# bonnet_floral.net
KiCad netlist of a schematic drawn in EAGLE
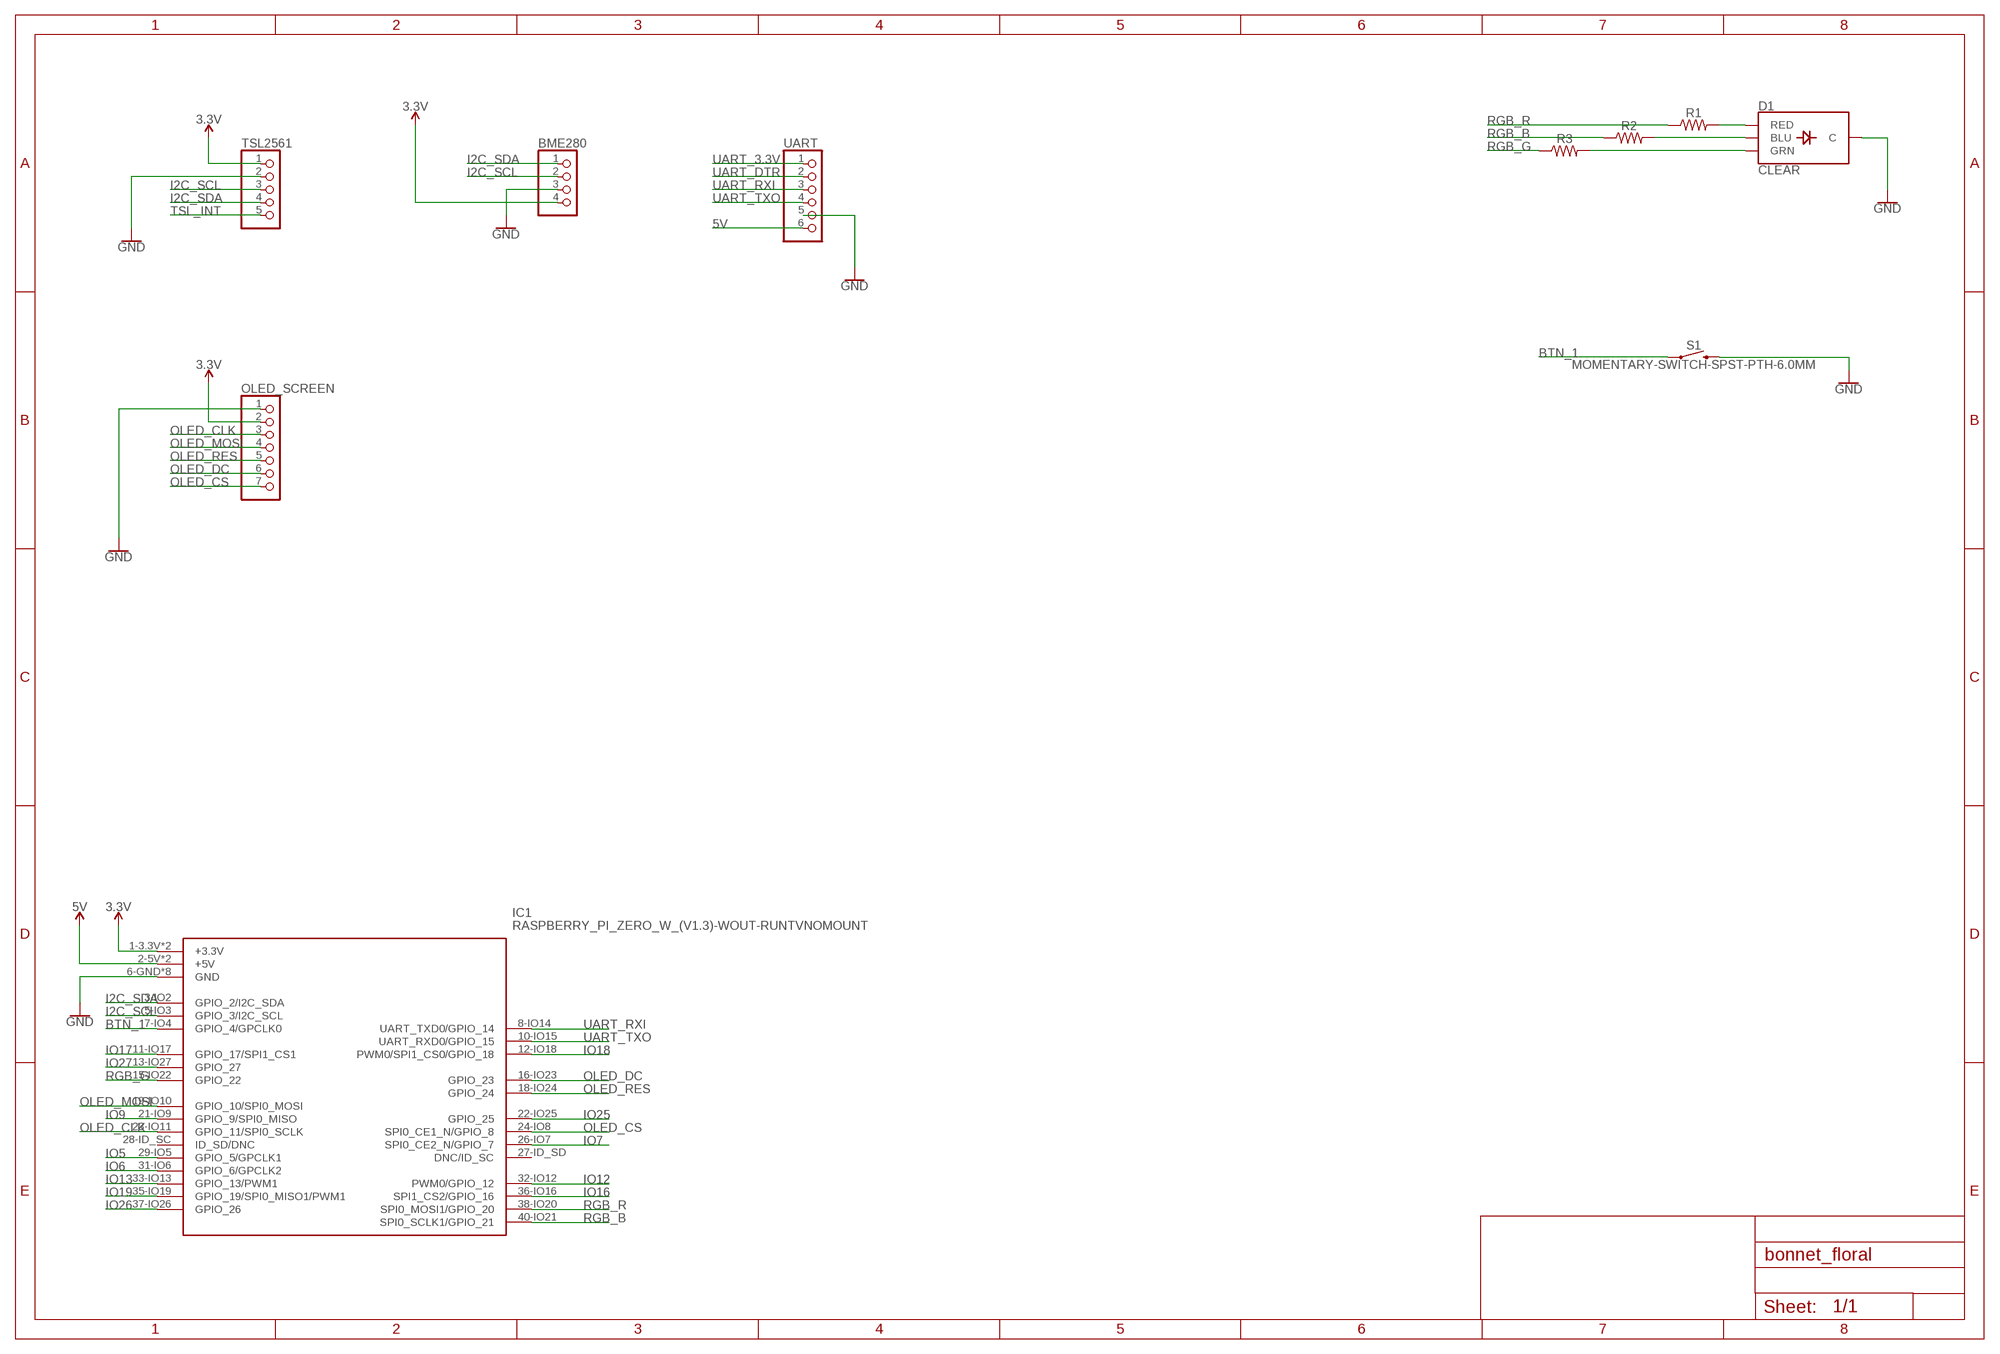
[diagram p0: schematic, sheet 1]

(export (version "E")
  (design (tool "Eeschema 10.0.6"))
  (components
    (comp (ref "BME280")
      (value "PINHD-1X4")
      (footprint "eagle-import:1X04")
      (libsource (lib "eagle-import") (part "PINHD-1X4"))
    )
    (comp (ref "D1")
      (value "CLEAR")
      (footprint "eagle-import:LED-RGB-THRU@1")
      (libsource (lib "eagle-import") (part "LED-RGB-CCCLEAR"))
    )
    (comp (ref "IC1")
      (value "RASPBERRY_PI_ZERO_W_(V1.3)-WOUT-RUNTVNOMOUNT")
      (footprint "eagle-import:RASPBERRYPIZEROWV13-WOUT-RUNTV-NOMOUNT")
      (libsource (lib "eagle-import") (part "RASPBERRY_PI_ZERO_W_(V1.3)-WOUT-RUNTVNOMOUNT"))
    )
    (comp (ref "OLED_SCREEN")
      (value "PINHD-1X7")
      (footprint "eagle-import:1X07")
      (libsource (lib "eagle-import") (part "PINHD-1X7"))
    )
    (comp (ref "R1")
      (value "RESISTORAXIAL-0.3")
      (footprint "eagle-import:AXIAL-0.3")
      (libsource (lib "eagle-import") (part "RESISTORAXIAL-0.3"))
    )
    (comp (ref "R2")
      (value "RESISTORAXIAL-0.3")
      (footprint "eagle-import:AXIAL-0.3")
      (libsource (lib "eagle-import") (part "RESISTORAXIAL-0.3"))
    )
    (comp (ref "R3")
      (value "RESISTORAXIAL-0.3")
      (footprint "eagle-import:AXIAL-0.3")
      (libsource (lib "eagle-import") (part "RESISTORAXIAL-0.3"))
    )
    (comp (ref "S1")
      (value "MOMENTARY-SWITCH-SPST-PTH-6.0MM")
      (footprint "eagle-import:TACTILE_SWITCH_PTH_6.0MM")
      (libsource (lib "eagle-import") (part "MOMENTARY-SWITCH-SPST-PTH-6.0MM"))
    )
    (comp (ref "TSL2561")
      (value "PINHD-1X5")
      (footprint "eagle-import:1X05")
      (libsource (lib "eagle-import") (part "PINHD-1X5"))
    )
    (comp (ref "UART")
      (value "PINHD-1X6")
      (footprint "eagle-import:1X06")
      (libsource (lib "eagle-import") (part "PINHD-1X6"))
    )
  )
  (nets
    (net (code "1") (name "/BTN_1") (class "Default")
      (node (ref "IC1") (pin "7-IO4") (pinfunction "GPIO_4/GPCLK0_7-IO4") (pintype "bidirectional"))
      (node (ref "S1") (pin "1") (pinfunction "1_1") (pintype "passive"))
    )
    (net (code "2") (name "/I2C_SCL") (class "Default")
      (node (ref "BME280") (pin "2") (pinfunction "2_2") (pintype "passive"))
      (node (ref "IC1") (pin "5-IO3") (pinfunction "GPIO_3/I2C_SCL_5-IO3") (pintype "bidirectional"))
      (node (ref "TSL2561") (pin "3") (pinfunction "3_3") (pintype "passive"))
    )
    (net (code "3") (name "/I2C_SDA") (class "Default")
      (node (ref "BME280") (pin "1") (pinfunction "1_1") (pintype "passive"))
      (node (ref "IC1") (pin "3-IO2") (pinfunction "GPIO_2/I2C_SDA_3-IO2") (pintype "bidirectional"))
      (node (ref "TSL2561") (pin "4") (pinfunction "4_4") (pintype "passive"))
    )
    (net (code "4") (name "/IO5") (class "Default")
      (node (ref "IC1") (pin "29-IO5") (pinfunction "GPIO_5/GPCLK1_29-IO5") (pintype "bidirectional"))
    )
    (net (code "5") (name "/IO6") (class "Default")
      (node (ref "IC1") (pin "31-IO6") (pinfunction "GPIO_6/GPCLK2_31-IO6") (pintype "bidirectional"))
    )
    (net (code "6") (name "/IO7") (class "Default")
      (node (ref "IC1") (pin "26-IO7") (pinfunction "SPI0_CE2_N/GPIO_7_26-IO7") (pintype "bidirectional"))
    )
    (net (code "7") (name "/IO9") (class "Default")
      (node (ref "IC1") (pin "21-IO9") (pinfunction "GPIO_9/SPI0_MISO_21-IO9") (pintype "bidirectional"))
    )
    (net (code "8") (name "/IO12") (class "Default")
      (node (ref "IC1") (pin "32-IO12") (pinfunction "PWM0/GPIO_12_32-IO12") (pintype "bidirectional"))
    )
    (net (code "9") (name "/IO13") (class "Default")
      (node (ref "IC1") (pin "33-IO13") (pinfunction "GPIO_13/PWM1_33-IO13") (pintype "bidirectional"))
    )
    (net (code "10") (name "/IO16") (class "Default")
      (node (ref "IC1") (pin "36-IO16") (pinfunction "SPI1_CS2/GPIO_16_36-IO16") (pintype "bidirectional"))
    )
    (net (code "11") (name "/IO17") (class "Default")
      (node (ref "IC1") (pin "11-IO17") (pinfunction "GPIO_17/SPI1_CS1_11-IO17") (pintype "bidirectional"))
    )
    (net (code "12") (name "/IO18") (class "Default")
      (node (ref "IC1") (pin "12-IO18") (pinfunction "PWM0/SPI1_CS0/GPIO_18_12-IO18") (pintype "bidirectional"))
    )
    (net (code "13") (name "/IO19") (class "Default")
      (node (ref "IC1") (pin "35-IO19") (pinfunction "GPIO_19/SPI0_MISO1/PWM1_35-IO19") (pintype "bidirectional"))
    )
    (net (code "14") (name "/IO25") (class "Default")
      (node (ref "IC1") (pin "22-IO25") (pinfunction "GPIO_25_22-IO25") (pintype "bidirectional"))
    )
    (net (code "15") (name "/IO26") (class "Default")
      (node (ref "IC1") (pin "37-IO26") (pinfunction "GPIO_26_37-IO26") (pintype "bidirectional"))
    )
    (net (code "16") (name "/IO27") (class "Default")
      (node (ref "IC1") (pin "13-IO27") (pinfunction "GPIO_27_13-IO27") (pintype "bidirectional"))
    )
    (net (code "17") (name "/OLED_CLK") (class "Default")
      (node (ref "IC1") (pin "23-IO11") (pinfunction "GPIO_11/SPI0_SCLK_23-IO11") (pintype "bidirectional"))
      (node (ref "OLED_SCREEN") (pin "3") (pinfunction "3_3") (pintype "passive"))
    )
    (net (code "18") (name "/OLED_CS") (class "Default")
      (node (ref "IC1") (pin "24-IO8") (pinfunction "SPI0_CE1_N/GPIO_8_24-IO8") (pintype "bidirectional"))
      (node (ref "OLED_SCREEN") (pin "7") (pinfunction "7_7") (pintype "passive"))
    )
    (net (code "19") (name "/OLED_DC") (class "Default")
      (node (ref "IC1") (pin "16-IO23") (pinfunction "GPIO_23_16-IO23") (pintype "bidirectional"))
      (node (ref "OLED_SCREEN") (pin "6") (pinfunction "6_6") (pintype "passive"))
    )
    (net (code "20") (name "/OLED_MOSI") (class "Default")
      (node (ref "IC1") (pin "19-IO10") (pinfunction "GPIO_10/SPI0_MOSI_19-IO10") (pintype "bidirectional"))
      (node (ref "OLED_SCREEN") (pin "4") (pinfunction "4_4") (pintype "passive"))
    )
    (net (code "21") (name "/OLED_RES") (class "Default")
      (node (ref "IC1") (pin "18-IO24") (pinfunction "GPIO_24_18-IO24") (pintype "bidirectional"))
      (node (ref "OLED_SCREEN") (pin "5") (pinfunction "5_5") (pintype "passive"))
    )
    (net (code "22") (name "/RGB_B") (class "Default")
      (node (ref "IC1") (pin "40-IO21") (pinfunction "SPI0_SCLK1/GPIO_21_40-IO21") (pintype "bidirectional"))
      (node (ref "R2") (pin "P$1") (pinfunction "1_P$1") (pintype "passive"))
    )
    (net (code "23") (name "/RGB_G") (class "Default")
      (node (ref "IC1") (pin "15-IO22") (pinfunction "GPIO_22_15-IO22") (pintype "bidirectional"))
      (node (ref "R3") (pin "P$1") (pinfunction "1_P$1") (pintype "passive"))
    )
    (net (code "24") (name "/RGB_R") (class "Default")
      (node (ref "IC1") (pin "38-IO20") (pinfunction "SPI0_MOSI1/GPIO_20_38-IO20") (pintype "bidirectional"))
      (node (ref "R1") (pin "P$1") (pinfunction "1_P$1") (pintype "passive"))
    )
    (net (code "25") (name "/TSL_INT") (class "Default")
      (node (ref "TSL2561") (pin "5") (pinfunction "5_5") (pintype "passive"))
    )
    (net (code "26") (name "/UART_3.3V") (class "Default")
      (node (ref "UART") (pin "1") (pinfunction "1_1") (pintype "passive"))
    )
    (net (code "27") (name "/UART_DTR") (class "Default")
      (node (ref "UART") (pin "2") (pinfunction "2_2") (pintype "passive"))
    )
    (net (code "28") (name "/UART_RXI") (class "Default")
      (node (ref "IC1") (pin "8-IO14") (pinfunction "UART_TXD0/GPIO_14_8-IO14") (pintype "bidirectional"))
      (node (ref "UART") (pin "3") (pinfunction "3_3") (pintype "passive"))
    )
    (net (code "29") (name "/UART_TXO") (class "Default")
      (node (ref "IC1") (pin "10-IO15") (pinfunction "UART_RXD0/GPIO_15_10-IO15") (pintype "bidirectional"))
      (node (ref "UART") (pin "4") (pinfunction "4_4") (pintype "passive"))
    )
    (net (code "30") (name "3.3V") (class "Default")
      (node (ref "BME280") (pin "4") (pinfunction "4_4") (pintype "passive"))
      (node (ref "IC1") (pin "1-3.3V") (pinfunction "+3.3V_1-3.3V") (pintype "bidirectional"))
      (node (ref "IC1") (pin "17-3.3V") (pinfunction "+3.3V_17-3.3V") (pintype "bidirectional"))
      (node (ref "OLED_SCREEN") (pin "2") (pinfunction "2_2") (pintype "passive"))
      (node (ref "TSL2561") (pin "1") (pinfunction "1_1") (pintype "passive"))
    )
    (net (code "31") (name "5V") (class "Default")
      (node (ref "IC1") (pin "2-5V") (pinfunction "+5V_2-5V") (pintype "bidirectional"))
      (node (ref "IC1") (pin "4-5V") (pinfunction "+5V_4-5V") (pintype "bidirectional"))
      (node (ref "UART") (pin "6") (pinfunction "6_6") (pintype "passive"))
    )
    (net (code "32") (name "GND") (class "Default")
      (node (ref "BME280") (pin "3") (pinfunction "3_3") (pintype "passive"))
      (node (ref "D1") (pin "2") (pinfunction "C_2") (pintype "bidirectional"))
      (node (ref "IC1") (pin "14-GND") (pinfunction "GND_14-GND") (pintype "bidirectional"))
      (node (ref "IC1") (pin "20-GND") (pinfunction "GND_20-GND") (pintype "bidirectional"))
      (node (ref "IC1") (pin "25-GND") (pinfunction "GND_25-GND") (pintype "bidirectional"))
      (node (ref "IC1") (pin "30-GND") (pinfunction "GND_30-GND") (pintype "bidirectional"))
      (node (ref "IC1") (pin "34-GND") (pinfunction "GND_34-GND") (pintype "bidirectional"))
      (node (ref "IC1") (pin "39-GND") (pinfunction "GND_39-GND") (pintype "bidirectional"))
      (node (ref "IC1") (pin "6-GND") (pinfunction "GND_6-GND") (pintype "bidirectional"))
      (node (ref "IC1") (pin "9-GND") (pinfunction "GND_9-GND") (pintype "bidirectional"))
      (node (ref "OLED_SCREEN") (pin "1") (pinfunction "1_1") (pintype "passive"))
      (node (ref "S1") (pin "3") (pinfunction "2_3") (pintype "passive"))
      (node (ref "TSL2561") (pin "2") (pinfunction "2_2") (pintype "passive"))
      (node (ref "UART") (pin "5") (pinfunction "5_5") (pintype "passive"))
    )
    (net (code "33") (name "Net-(D1-BLU)") (class "Default")
      (node (ref "D1") (pin "4") (pinfunction "BLU_4") (pintype "bidirectional"))
      (node (ref "R2") (pin "P$2") (pinfunction "2_P$2") (pintype "passive"))
    )
    (net (code "34") (name "Net-(D1-GRN)") (class "Default")
      (node (ref "D1") (pin "3") (pinfunction "GRN_3") (pintype "bidirectional"))
      (node (ref "R3") (pin "P$2") (pinfunction "2_P$2") (pintype "passive"))
    )
    (net (code "35") (name "Net-(D1-RED)") (class "Default")
      (node (ref "D1") (pin "1") (pinfunction "RED_1") (pintype "bidirectional"))
      (node (ref "R1") (pin "P$2") (pinfunction "2_P$2") (pintype "passive"))
    )
    (net (code "36") (name "unconnected-(IC1-DNC{slash}ID_SC-Pad27-ID_SD)") (class "Default")
      (node (ref "IC1") (pin "27-ID_SD") (pinfunction "DNC/ID_SC_27-ID_SD") (pintype "bidirectional"))
    )
    (net (code "37") (name "unconnected-(IC1-ID_SD{slash}DNC-Pad28-ID_SC)") (class "Default")
      (node (ref "IC1") (pin "28-ID_SC") (pinfunction "ID_SD/DNC_28-ID_SC") (pintype "bidirectional"))
    )
  )
)
